# PocketSDR_Discovery.net
KiCad netlist of a schematic drawn in EAGLE
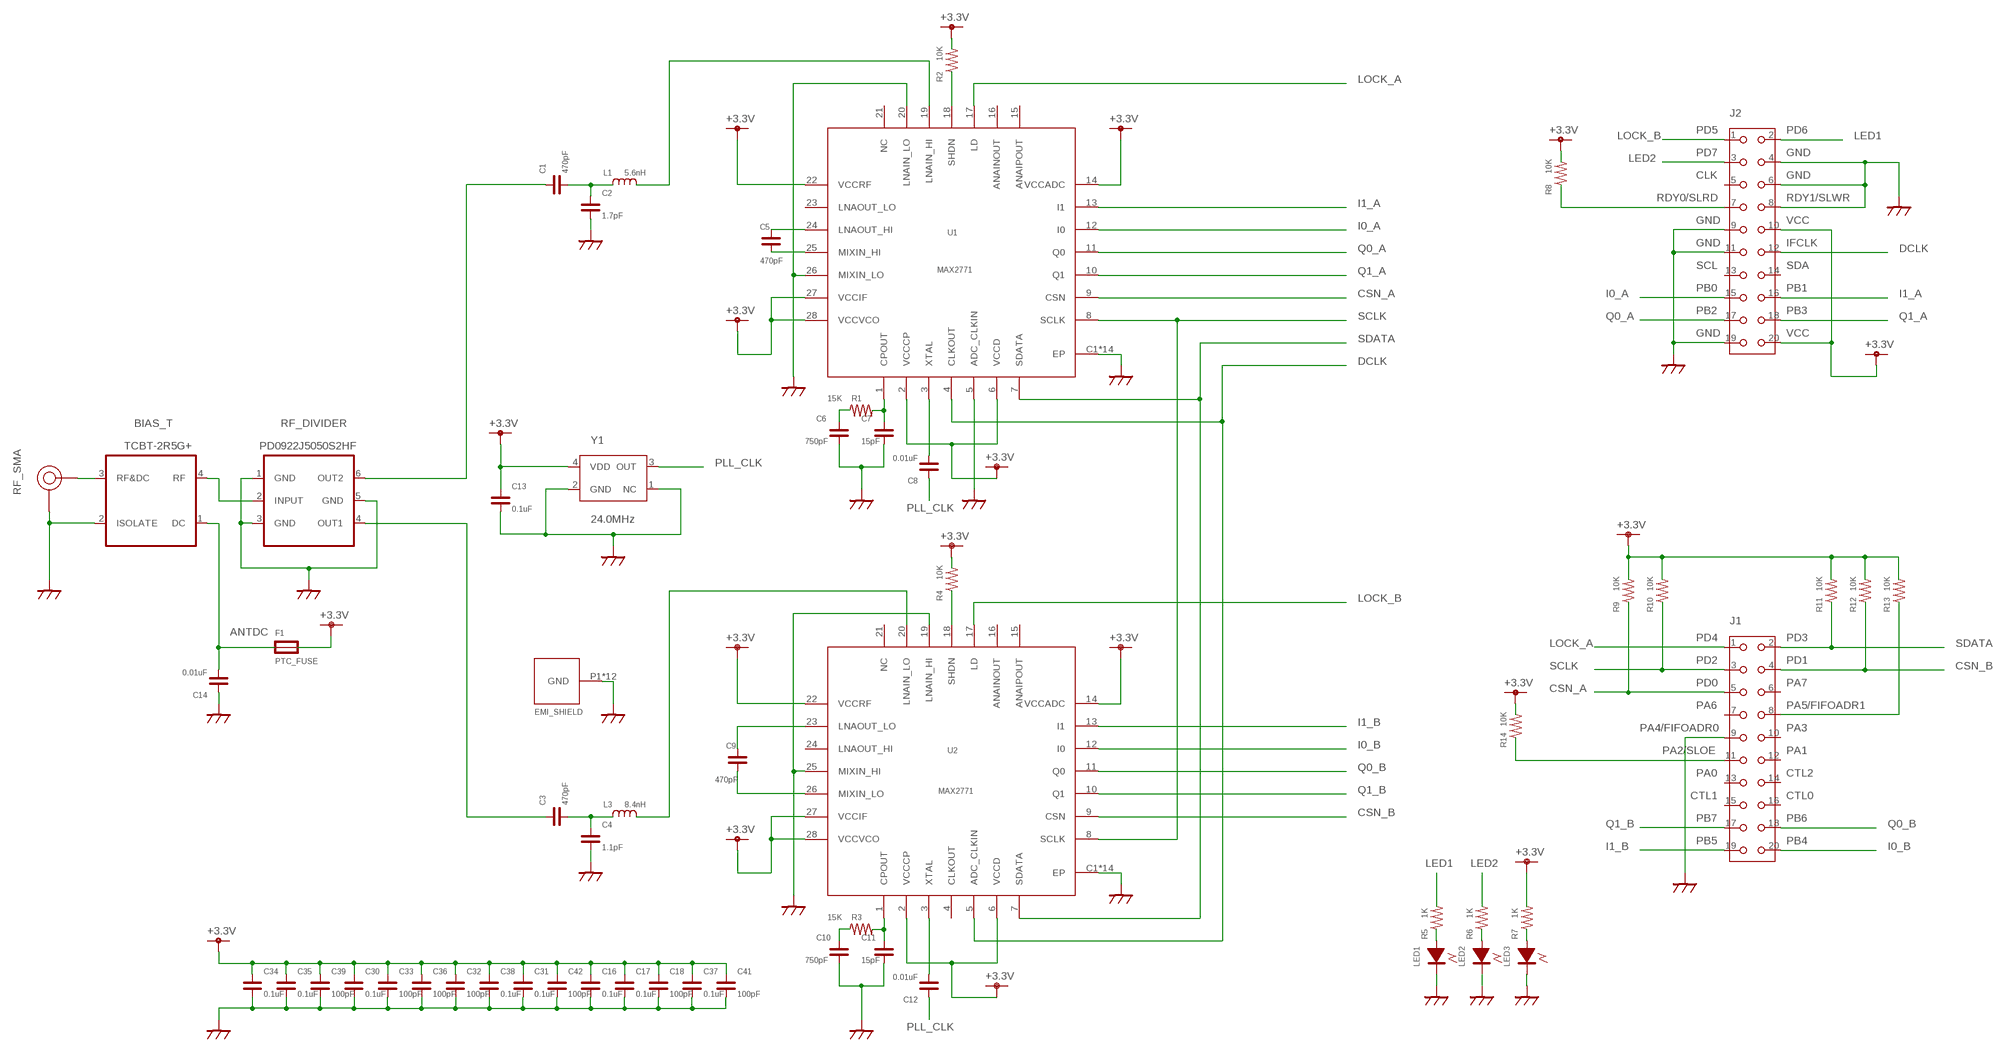
[diagram p0: schematic, sheet 1]

(export (version "E")
  (design (tool "Eeschema 10.0.6"))
  (components
    (comp (ref "BIAS_T")
      (value "TCBT-2R5G+")
      (footprint "eagle-import:BIAS_T")
      (libsource (lib "eagle-import") (part "BIAS_T"))
    )
    (comp (ref "C1")
      (value "470pF")
      (footprint "eagle-import:C1005")
      (libsource (lib "eagle-import") (part "C1005"))
    )
    (comp (ref "C2")
      (value "1.7pF")
      (footprint "eagle-import:C1005")
      (libsource (lib "eagle-import") (part "C1005"))
    )
    (comp (ref "C3")
      (value "470pF")
      (footprint "eagle-import:C1005")
      (libsource (lib "eagle-import") (part "C1005"))
    )
    (comp (ref "C4")
      (value "1.1pF")
      (footprint "eagle-import:C1005")
      (libsource (lib "eagle-import") (part "C1005"))
    )
    (comp (ref "C5")
      (value "470pF")
      (footprint "eagle-import:C1005")
      (libsource (lib "eagle-import") (part "C1005"))
    )
    (comp (ref "C6")
      (value "750pF")
      (footprint "eagle-import:C1005")
      (libsource (lib "eagle-import") (part "C1005"))
    )
    (comp (ref "C7")
      (value "15pF")
      (footprint "eagle-import:C1005")
      (libsource (lib "eagle-import") (part "C1005"))
    )
    (comp (ref "C8")
      (value "0.01uF")
      (footprint "eagle-import:C1005")
      (libsource (lib "eagle-import") (part "C1005"))
    )
    (comp (ref "C9")
      (value "470pF")
      (footprint "eagle-import:C1005")
      (libsource (lib "eagle-import") (part "C1005"))
    )
    (comp (ref "C10")
      (value "750pF")
      (footprint "eagle-import:C1005")
      (libsource (lib "eagle-import") (part "C1005"))
    )
    (comp (ref "C11")
      (value "15pF")
      (footprint "eagle-import:C1005")
      (libsource (lib "eagle-import") (part "C1005"))
    )
    (comp (ref "C12")
      (value "0.01uF")
      (footprint "eagle-import:C1005")
      (libsource (lib "eagle-import") (part "C1005"))
    )
    (comp (ref "C13")
      (value "0.1uF")
      (footprint "eagle-import:C1005")
      (libsource (lib "eagle-import") (part "C1005"))
    )
    (comp (ref "C14")
      (value "0.01uF")
      (footprint "eagle-import:C1005")
      (libsource (lib "eagle-import") (part "C1005"))
    )
    (comp (ref "C16")
      (value "0.1uF")
      (footprint "eagle-import:C1005")
      (libsource (lib "eagle-import") (part "C1005"))
    )
    (comp (ref "C17")
      (value "0.1uF")
      (footprint "eagle-import:C1005")
      (libsource (lib "eagle-import") (part "C1005"))
    )
    (comp (ref "C18")
      (value "100pF")
      (footprint "eagle-import:C1005")
      (libsource (lib "eagle-import") (part "C1005"))
    )
    (comp (ref "C30")
      (value "0.1uF")
      (footprint "eagle-import:C1005")
      (libsource (lib "eagle-import") (part "C1005"))
    )
    (comp (ref "C31")
      (value "0.1uF")
      (footprint "eagle-import:C1005")
      (libsource (lib "eagle-import") (part "C1005"))
    )
    (comp (ref "C32")
      (value "100pF")
      (footprint "eagle-import:C1005")
      (libsource (lib "eagle-import") (part "C1005"))
    )
    (comp (ref "C33")
      (value "100pF")
      (footprint "eagle-import:C1005")
      (libsource (lib "eagle-import") (part "C1005"))
    )
    (comp (ref "C34")
      (value "0.1uF")
      (footprint "eagle-import:C1005")
      (libsource (lib "eagle-import") (part "C1005"))
    )
    (comp (ref "C35")
      (value "0.1uF")
      (footprint "eagle-import:C1005")
      (libsource (lib "eagle-import") (part "C1005"))
    )
    (comp (ref "C36")
      (value "100pF")
      (footprint "eagle-import:C1005")
      (libsource (lib "eagle-import") (part "C1005"))
    )
    (comp (ref "C37")
      (value "0.1uF")
      (footprint "eagle-import:C1005")
      (libsource (lib "eagle-import") (part "C1005"))
    )
    (comp (ref "C38")
      (value "0.1uF")
      (footprint "eagle-import:C1005")
      (libsource (lib "eagle-import") (part "C1005"))
    )
    (comp (ref "C39")
      (value "100pF")
      (footprint "eagle-import:C1005")
      (libsource (lib "eagle-import") (part "C1005"))
    )
    (comp (ref "C41")
      (value "100pF")
      (footprint "eagle-import:C1005")
      (libsource (lib "eagle-import") (part "C1005"))
    )
    (comp (ref "C42")
      (value "100pF")
      (footprint "eagle-import:C1005")
      (libsource (lib "eagle-import") (part "C1005"))
    )
    (comp (ref "F1")
      (value "PTC_FUSE")
      (footprint "eagle-import:C1608")
      (libsource (lib "eagle-import") (part "PTC_FUSE"))
    )
    (comp (ref "J1")
      (value "PINH-2.54MM-20P")
      (footprint "eagle-import:PINH-2.54MM-20P")
      (libsource (lib "eagle-import") (part "PINH-2.54MM-20P"))
    )
    (comp (ref "J2")
      (value "PINH-2.54MM-20P")
      (footprint "eagle-import:PINH-2.54MM-20P")
      (libsource (lib "eagle-import") (part "PINH-2.54MM-20P"))
    )
    (comp (ref "L1")
      (value "5.6nH")
      (footprint "eagle-import:C1608")
      (libsource (lib "eagle-import") (part "L1608"))
    )
    (comp (ref "L3")
      (value "8.4nH")
      (footprint "eagle-import:C1608")
      (libsource (lib "eagle-import") (part "L1608"))
    )
    (comp (ref "LED1")
      (value "LED1608")
      (footprint "eagle-import:LED_1608")
      (libsource (lib "eagle-import") (part "LED1608"))
    )
    (comp (ref "LED2")
      (value "LED1608")
      (footprint "eagle-import:LED_1608")
      (libsource (lib "eagle-import") (part "LED1608"))
    )
    (comp (ref "LED3")
      (value "LED1608")
      (footprint "eagle-import:LED_1608")
      (libsource (lib "eagle-import") (part "LED1608"))
    )
    (comp (ref "R1")
      (value "15K")
      (footprint "eagle-import:C1005")
      (libsource (lib "eagle-import") (part "R1005"))
    )
    (comp (ref "R2")
      (value "10K")
      (footprint "eagle-import:C1005")
      (libsource (lib "eagle-import") (part "R1005"))
    )
    (comp (ref "R3")
      (value "15K")
      (footprint "eagle-import:C1005")
      (libsource (lib "eagle-import") (part "R1005"))
    )
    (comp (ref "R4")
      (value "10K")
      (footprint "eagle-import:C1005")
      (libsource (lib "eagle-import") (part "R1005"))
    )
    (comp (ref "R5")
      (value "1K")
      (footprint "eagle-import:C1005")
      (libsource (lib "eagle-import") (part "R1005"))
    )
    (comp (ref "R6")
      (value "1K")
      (footprint "eagle-import:C1005")
      (libsource (lib "eagle-import") (part "R1005"))
    )
    (comp (ref "R7")
      (value "1K")
      (footprint "eagle-import:C1005")
      (libsource (lib "eagle-import") (part "R1005"))
    )
    (comp (ref "R8")
      (value "10K")
      (footprint "eagle-import:C1005")
      (libsource (lib "eagle-import") (part "R1005"))
    )
    (comp (ref "R9")
      (value "10K")
      (footprint "eagle-import:C1005")
      (libsource (lib "eagle-import") (part "R1005"))
    )
    (comp (ref "R10")
      (value "10K")
      (footprint "eagle-import:C1005")
      (libsource (lib "eagle-import") (part "R1005"))
    )
    (comp (ref "R11")
      (value "10K")
      (footprint "eagle-import:C1005")
      (libsource (lib "eagle-import") (part "R1005"))
    )
    (comp (ref "R12")
      (value "10K")
      (footprint "eagle-import:C1005")
      (libsource (lib "eagle-import") (part "R1005"))
    )
    (comp (ref "R13")
      (value "10K")
      (footprint "eagle-import:C1005")
      (libsource (lib "eagle-import") (part "R1005"))
    )
    (comp (ref "R14")
      (value "10K")
      (footprint "eagle-import:C1005")
      (libsource (lib "eagle-import") (part "R1005"))
    )
    (comp (ref "RF-SHEILD-CASE")
      (value "BMI-S-202-F BMI-S-202-C")
      (footprint "eagle-import:BMI-S-202")
      (libsource (lib "eagle-import") (part "BMI-S-202"))
    )
    (comp (ref "RF_DIVIDER")
      (value "PD0922J5050S2HF")
      (footprint "eagle-import:RF_DIV")
      (libsource (lib "eagle-import") (part "RF_DIV"))
    )
    (comp (ref "RF_SMA")
      (value "SMA JACK EDGE MNT")
      (footprint "eagle-import:SMA-ANG")
      (libsource (lib "eagle-import") (part "SMA-ANG"))
    )
    (comp (ref "U1")
      (value "MAX2771")
      (footprint "eagle-import:TQFN28")
      (libsource (lib "eagle-import") (part "MAX2771"))
    )
    (comp (ref "U2")
      (value "MAX2771")
      (footprint "eagle-import:TQFN28")
      (libsource (lib "eagle-import") (part "MAX2771"))
    )
    (comp (ref "Y1")
      (value "24.0MHz")
      (footprint "eagle-import:TCXO2520")
      (libsource (lib "eagle-import") (part "TCXO2520"))
    )
  )
  (nets
    (net (code "1") (name "+3.3V") (class "Default")
      (node (ref "C13") (pin "1") (pinfunction "1_1") (pintype "passive"))
      (node (ref "C16") (pin "1") (pinfunction "1_1") (pintype "passive"))
      (node (ref "C17") (pin "1") (pinfunction "1_1") (pintype "passive"))
      (node (ref "C18") (pin "1") (pinfunction "1_1") (pintype "passive"))
      (node (ref "C30") (pin "1") (pinfunction "1_1") (pintype "passive"))
      (node (ref "C31") (pin "1") (pinfunction "1_1") (pintype "passive"))
      (node (ref "C32") (pin "1") (pinfunction "1_1") (pintype "passive"))
      (node (ref "C33") (pin "1") (pinfunction "1_1") (pintype "passive"))
      (node (ref "C34") (pin "1") (pinfunction "1_1") (pintype "passive"))
      (node (ref "C35") (pin "1") (pinfunction "1_1") (pintype "passive"))
      (node (ref "C36") (pin "1") (pinfunction "1_1") (pintype "passive"))
      (node (ref "C37") (pin "1") (pinfunction "1_1") (pintype "passive"))
      (node (ref "C38") (pin "1") (pinfunction "1_1") (pintype "passive"))
      (node (ref "C39") (pin "1") (pinfunction "1_1") (pintype "passive"))
      (node (ref "C41") (pin "1") (pinfunction "1_1") (pintype "passive"))
      (node (ref "C42") (pin "1") (pinfunction "1_1") (pintype "passive"))
      (node (ref "F1") (pin "2") (pinfunction "P$2_2") (pintype "bidirectional"))
      (node (ref "J2") (pin "10") (pinfunction "P10_10") (pintype "bidirectional"))
      (node (ref "J2") (pin "20") (pinfunction "P20_20") (pintype "bidirectional"))
      (node (ref "R10") (pin "2") (pinfunction "P$2_2") (pintype "passive"))
      (node (ref "R11") (pin "2") (pinfunction "P$2_2") (pintype "passive"))
      (node (ref "R12") (pin "2") (pinfunction "P$2_2") (pintype "passive"))
      (node (ref "R13") (pin "2") (pinfunction "P$2_2") (pintype "passive"))
      (node (ref "R14") (pin "2") (pinfunction "P$2_2") (pintype "passive"))
      (node (ref "R2") (pin "2") (pinfunction "P$2_2") (pintype "passive"))
      (node (ref "R4") (pin "2") (pinfunction "P$2_2") (pintype "passive"))
      (node (ref "R7") (pin "2") (pinfunction "P$2_2") (pintype "passive"))
      (node (ref "R8") (pin "2") (pinfunction "P$2_2") (pintype "passive"))
      (node (ref "R9") (pin "2") (pinfunction "P$2_2") (pintype "passive"))
      (node (ref "U1") (pin "14") (pinfunction "VCCADC_14") (pintype "power_in"))
      (node (ref "U1") (pin "2") (pinfunction "VCCCP_2") (pintype "power_in"))
      (node (ref "U1") (pin "22") (pinfunction "VCCRF_22") (pintype "power_in"))
      (node (ref "U1") (pin "27") (pinfunction "VCCIF_27") (pintype "power_in"))
      (node (ref "U1") (pin "28") (pinfunction "VCCVCO_28") (pintype "power_in"))
      (node (ref "U1") (pin "6") (pinfunction "VCCD_6") (pintype "power_in"))
      (node (ref "U2") (pin "14") (pinfunction "VCCADC_14") (pintype "power_in"))
      (node (ref "U2") (pin "2") (pinfunction "VCCCP_2") (pintype "power_in"))
      (node (ref "U2") (pin "22") (pinfunction "VCCRF_22") (pintype "power_in"))
      (node (ref "U2") (pin "27") (pinfunction "VCCIF_27") (pintype "power_in"))
      (node (ref "U2") (pin "28") (pinfunction "VCCVCO_28") (pintype "power_in"))
      (node (ref "U2") (pin "6") (pinfunction "VCCD_6") (pintype "power_in"))
      (node (ref "Y1") (pin "4") (pinfunction "VDD_4") (pintype "bidirectional"))
    )
    (net (code "2") (name "/ANTDC") (class "Default")
      (node (ref "BIAS_T") (pin "1") (pinfunction "DC_1") (pintype "bidirectional"))
      (node (ref "C14") (pin "2") (pinfunction "2_2") (pintype "passive"))
      (node (ref "F1") (pin "1") (pinfunction "P$1_1") (pintype "bidirectional"))
    )
    (net (code "3") (name "/CSN_A") (class "Default")
      (node (ref "J1") (pin "5") (pinfunction "P5_5") (pintype "bidirectional"))
      (node (ref "R9") (pin "1") (pinfunction "P$1_1") (pintype "passive"))
      (node (ref "U1") (pin "9") (pinfunction "CSN_9") (pintype "input"))
    )
    (net (code "4") (name "/CSN_B") (class "Default")
      (node (ref "J1") (pin "4") (pinfunction "P4_4") (pintype "bidirectional"))
      (node (ref "R12") (pin "1") (pinfunction "P$1_1") (pintype "passive"))
      (node (ref "U2") (pin "9") (pinfunction "CSN_9") (pintype "input"))
    )
    (net (code "5") (name "/DCLK") (class "Default")
      (node (ref "J2") (pin "12") (pinfunction "P12_12") (pintype "bidirectional"))
      (node (ref "U1") (pin "4") (pinfunction "CLKOUT_4") (pintype "bidirectional"))
      (node (ref "U2") (pin "5") (pinfunction "ADC_CLKIN_5") (pintype "bidirectional"))
    )
    (net (code "6") (name "/I0_A") (class "Default")
      (node (ref "J2") (pin "15") (pinfunction "P15_15") (pintype "bidirectional"))
      (node (ref "U1") (pin "12") (pinfunction "I0_12") (pintype "output"))
    )
    (net (code "7") (name "/I0_B") (class "Default")
      (node (ref "J1") (pin "20") (pinfunction "P20_20") (pintype "bidirectional"))
      (node (ref "U2") (pin "12") (pinfunction "I0_12") (pintype "output"))
    )
    (net (code "8") (name "/I1_A") (class "Default")
      (node (ref "J2") (pin "16") (pinfunction "P16_16") (pintype "bidirectional"))
      (node (ref "U1") (pin "13") (pinfunction "I1_13") (pintype "output"))
    )
    (net (code "9") (name "/I1_B") (class "Default")
      (node (ref "J1") (pin "19") (pinfunction "P19_19") (pintype "bidirectional"))
      (node (ref "U2") (pin "13") (pinfunction "I1_13") (pintype "output"))
    )
    (net (code "10") (name "/LED1") (class "Default")
      (node (ref "J2") (pin "2") (pinfunction "P2_2") (pintype "bidirectional"))
      (node (ref "R5") (pin "2") (pinfunction "P$2_2") (pintype "passive"))
    )
    (net (code "11") (name "/LED2") (class "Default")
      (node (ref "J2") (pin "3") (pinfunction "P3_3") (pintype "bidirectional"))
      (node (ref "R6") (pin "2") (pinfunction "P$2_2") (pintype "passive"))
    )
    (net (code "12") (name "/LOCK_A") (class "Default")
      (node (ref "J1") (pin "1") (pinfunction "P1_1") (pintype "bidirectional"))
      (node (ref "U1") (pin "17") (pinfunction "LD_17") (pintype "output"))
    )
    (net (code "13") (name "/LOCK_B") (class "Default")
      (node (ref "J2") (pin "1") (pinfunction "P1_1") (pintype "bidirectional"))
      (node (ref "U2") (pin "17") (pinfunction "LD_17") (pintype "output"))
    )
    (net (code "14") (name "/PLL_CLK") (class "Default")
      (node (ref "C12") (pin "1") (pinfunction "1_1") (pintype "passive"))
      (node (ref "C8") (pin "1") (pinfunction "1_1") (pintype "passive"))
      (node (ref "Y1") (pin "3") (pinfunction "OUT_3") (pintype "bidirectional"))
    )
    (net (code "15") (name "/Q0_A") (class "Default")
      (node (ref "J2") (pin "17") (pinfunction "P17_17") (pintype "bidirectional"))
      (node (ref "U1") (pin "11") (pinfunction "Q0_11") (pintype "output"))
    )
    (net (code "16") (name "/Q0_B") (class "Default")
      (node (ref "J1") (pin "18") (pinfunction "P18_18") (pintype "bidirectional"))
      (node (ref "U2") (pin "11") (pinfunction "Q0_11") (pintype "output"))
    )
    (net (code "17") (name "/Q1_A") (class "Default")
      (node (ref "J2") (pin "18") (pinfunction "P18_18") (pintype "bidirectional"))
      (node (ref "U1") (pin "10") (pinfunction "Q1_10") (pintype "output"))
    )
    (net (code "18") (name "/Q1_B") (class "Default")
      (node (ref "J1") (pin "17") (pinfunction "P17_17") (pintype "bidirectional"))
      (node (ref "U2") (pin "10") (pinfunction "Q1_10") (pintype "output"))
    )
    (net (code "19") (name "/SCLK") (class "Default")
      (node (ref "J1") (pin "3") (pinfunction "P3_3") (pintype "bidirectional"))
      (node (ref "R10") (pin "1") (pinfunction "P$1_1") (pintype "passive"))
      (node (ref "U1") (pin "8") (pinfunction "SCLK_8") (pintype "input"))
      (node (ref "U2") (pin "8") (pinfunction "SCLK_8") (pintype "input"))
    )
    (net (code "20") (name "/SDATA") (class "Default")
      (node (ref "J1") (pin "2") (pinfunction "P2_2") (pintype "bidirectional"))
      (node (ref "R11") (pin "1") (pinfunction "P$1_1") (pintype "passive"))
      (node (ref "U1") (pin "7") (pinfunction "SDATA_7") (pintype "bidirectional"))
      (node (ref "U2") (pin "7") (pinfunction "SDATA_7") (pintype "bidirectional"))
    )
    (net (code "21") (name "GND") (class "Default")
      (node (ref "BIAS_T") (pin "2") (pinfunction "ISOLATE_2") (pintype "bidirectional"))
      (node (ref "C10") (pin "2") (pinfunction "2_2") (pintype "passive"))
      (node (ref "C11") (pin "2") (pinfunction "2_2") (pintype "passive"))
      (node (ref "C13") (pin "2") (pinfunction "2_2") (pintype "passive"))
      (node (ref "C14") (pin "1") (pinfunction "1_1") (pintype "passive"))
      (node (ref "C16") (pin "2") (pinfunction "2_2") (pintype "passive"))
      (node (ref "C17") (pin "2") (pinfunction "2_2") (pintype "passive"))
      (node (ref "C18") (pin "2") (pinfunction "2_2") (pintype "passive"))
      (node (ref "C2") (pin "1") (pinfunction "1_1") (pintype "passive"))
      (node (ref "C30") (pin "2") (pinfunction "2_2") (pintype "passive"))
      (node (ref "C31") (pin "2") (pinfunction "2_2") (pintype "passive"))
      (node (ref "C32") (pin "2") (pinfunction "2_2") (pintype "passive"))
      (node (ref "C33") (pin "2") (pinfunction "2_2") (pintype "passive"))
      (node (ref "C34") (pin "2") (pinfunction "2_2") (pintype "passive"))
      (node (ref "C35") (pin "2") (pinfunction "2_2") (pintype "passive"))
      (node (ref "C36") (pin "2") (pinfunction "2_2") (pintype "passive"))
      (node (ref "C37") (pin "2") (pinfunction "2_2") (pintype "passive"))
      (node (ref "C38") (pin "2") (pinfunction "2_2") (pintype "passive"))
      (node (ref "C39") (pin "2") (pinfunction "2_2") (pintype "passive"))
      (node (ref "C4") (pin "2") (pinfunction "2_2") (pintype "passive"))
      (node (ref "C41") (pin "2") (pinfunction "2_2") (pintype "passive"))
      (node (ref "C42") (pin "2") (pinfunction "2_2") (pintype "passive"))
      (node (ref "C6") (pin "2") (pinfunction "2_2") (pintype "passive"))
      (node (ref "C7") (pin "2") (pinfunction "2_2") (pintype "passive"))
      (node (ref "J1") (pin "9") (pinfunction "P9_9") (pintype "bidirectional"))
      (node (ref "J2") (pin "11") (pinfunction "P11_11") (pintype "bidirectional"))
      (node (ref "J2") (pin "19") (pinfunction "P19_19") (pintype "bidirectional"))
      (node (ref "J2") (pin "4") (pinfunction "P4_4") (pintype "bidirectional"))
      (node (ref "J2") (pin "6") (pinfunction "P6_6") (pintype "bidirectional"))
      (node (ref "J2") (pin "8") (pinfunction "P8_8") (pintype "bidirectional"))
      (node (ref "J2") (pin "9") (pinfunction "P9_9") (pintype "bidirectional"))
      (node (ref "LED1") (pin "2") (pinfunction "P$2_2") (pintype "passive"))
      (node (ref "LED2") (pin "2") (pinfunction "P$2_2") (pintype "passive"))
      (node (ref "LED3") (pin "2") (pinfunction "P$2_2") (pintype "passive"))
      (node (ref "RF-SHEILD-CASE") (pin "P1") (pinfunction "GND_P1") (pintype "bidirectional"))
      (node (ref "RF-SHEILD-CASE") (pin "P10") (pinfunction "GND_P10") (pintype "bidirectional"))
      (node (ref "RF-SHEILD-CASE") (pin "P11") (pinfunction "GND_P11") (pintype "bidirectional"))
      (node (ref "RF-SHEILD-CASE") (pin "P12") (pinfunction "GND_P12") (pintype "bidirectional"))
      (node (ref "RF-SHEILD-CASE") (pin "P2") (pinfunction "GND_P2") (pintype "bidirectional"))
      (node (ref "RF-SHEILD-CASE") (pin "P3") (pinfunction "GND_P3") (pintype "bidirectional"))
      (node (ref "RF-SHEILD-CASE") (pin "P4") (pinfunction "GND_P4") (pintype "bidirectional"))
      (node (ref "RF-SHEILD-CASE") (pin "P5") (pinfunction "GND_P5") (pintype "bidirectional"))
      (node (ref "RF-SHEILD-CASE") (pin "P6") (pinfunction "GND_P6") (pintype "bidirectional"))
      (node (ref "RF-SHEILD-CASE") (pin "P7") (pinfunction "GND_P7") (pintype "bidirectional"))
      (node (ref "RF-SHEILD-CASE") (pin "P8") (pinfunction "GND_P8") (pintype "bidirectional"))
      (node (ref "RF-SHEILD-CASE") (pin "P9") (pinfunction "GND_P9") (pintype "bidirectional"))
      (node (ref "RF_DIVIDER") (pin "1") (pinfunction "GND_1") (pintype "bidirectional"))
      (node (ref "RF_DIVIDER") (pin "3") (pinfunction "GND_3") (pintype "bidirectional"))
      (node (ref "RF_DIVIDER") (pin "5") (pinfunction "GND_5") (pintype "bidirectional"))
      (node (ref "RF_SMA") (pin "P2") (pinfunction "GND_P2") (pintype "passive"))
      (node (ref "RF_SMA") (pin "P3") (pinfunction "GND_P3") (pintype "passive"))
      (node (ref "RF_SMA") (pin "P4") (pinfunction "GND_P4") (pintype "passive"))
      (node (ref "RF_SMA") (pin "P5") (pinfunction "GND_P5") (pintype "passive"))
      (node (ref "U1") (pin "20") (pinfunction "LNAIN_LO_20") (pintype "bidirectional"))
      (node (ref "U1") (pin "26") (pinfunction "MIXIN_LO_26") (pintype "input"))
      (node (ref "U1") (pin "5") (pinfunction "ADC_CLKIN_5") (pintype "bidirectional"))
      (node (ref "U1") (pin "C1") (pinfunction "EP_C1") (pintype "power_in"))
      (node (ref "U1") (pin "C2") (pinfunction "EP_C2") (pintype "power_in"))
      (node (ref "U1") (pin "C3") (pinfunction "EP_C3") (pintype "power_in"))
      (node (ref "U1") (pin "C4") (pinfunction "EP_C4") (pintype "power_in"))
      (node (ref "U1") (pin "EP") (pinfunction "EP_EP") (pintype "power_in"))
      (node (ref "U1") (pin "V1") (pinfunction "EP_V1") (pintype "power_in"))
      (node (ref "U1") (pin "V2") (pinfunction "EP_V2") (pintype "power_in"))
      (node (ref "U1") (pin "V3") (pinfunction "EP_V3") (pintype "power_in"))
      (node (ref "U1") (pin "V4") (pinfunction "EP_V4") (pintype "power_in"))
      (node (ref "U1") (pin "V5") (pinfunction "EP_V5") (pintype "power_in"))
      (node (ref "U1") (pin "V6") (pinfunction "EP_V6") (pintype "power_in"))
      (node (ref "U1") (pin "V7") (pinfunction "EP_V7") (pintype "power_in"))
      (node (ref "U1") (pin "V8") (pinfunction "EP_V8") (pintype "power_in"))
      (node (ref "U1") (pin "V9") (pinfunction "EP_V9") (pintype "power_in"))
      (node (ref "U2") (pin "19") (pinfunction "LNAIN_HI_19") (pintype "bidirectional"))
      (node (ref "U2") (pin "25") (pinfunction "MIXIN_HI_25") (pintype "input"))
      (node (ref "U2") (pin "C1") (pinfunction "EP_C1") (pintype "power_in"))
      (node (ref "U2") (pin "C2") (pinfunction "EP_C2") (pintype "power_in"))
      (node (ref "U2") (pin "C3") (pinfunction "EP_C3") (pintype "power_in"))
      (node (ref "U2") (pin "C4") (pinfunction "EP_C4") (pintype "power_in"))
      (node (ref "U2") (pin "EP") (pinfunction "EP_EP") (pintype "power_in"))
      (node (ref "U2") (pin "V1") (pinfunction "EP_V1") (pintype "power_in"))
      (node (ref "U2") (pin "V2") (pinfunction "EP_V2") (pintype "power_in"))
      (node (ref "U2") (pin "V3") (pinfunction "EP_V3") (pintype "power_in"))
      (node (ref "U2") (pin "V4") (pinfunction "EP_V4") (pintype "power_in"))
      (node (ref "U2") (pin "V5") (pinfunction "EP_V5") (pintype "power_in"))
      (node (ref "U2") (pin "V6") (pinfunction "EP_V6") (pintype "power_in"))
      (node (ref "U2") (pin "V7") (pinfunction "EP_V7") (pintype "power_in"))
      (node (ref "U2") (pin "V8") (pinfunction "EP_V8") (pintype "power_in"))
      (node (ref "U2") (pin "V9") (pinfunction "EP_V9") (pintype "power_in"))
      (node (ref "Y1") (pin "1") (pinfunction "NC_1") (pintype "bidirectional"))
      (node (ref "Y1") (pin "2") (pinfunction "GND_2") (pintype "bidirectional"))
    )
    (net (code "22") (name "Net-(BIAS_T-RF&DC)") (class "Default")
      (node (ref "BIAS_T") (pin "3") (pinfunction "RF&DC_3") (pintype "bidirectional"))
      (node (ref "RF_SMA") (pin "P1") (pinfunction "RF_P1") (pintype "passive"))
    )
    (net (code "23") (name "Net-(BIAS_T-RF)") (class "Default")
      (node (ref "BIAS_T") (pin "4") (pinfunction "RF_4") (pintype "bidirectional"))
      (node (ref "RF_DIVIDER") (pin "2") (pinfunction "INPUT_2") (pintype "input"))
    )
    (net (code "24") (name "Net-(J1-P8)") (class "Default")
      (node (ref "J1") (pin "8") (pinfunction "P8_8") (pintype "bidirectional"))
      (node (ref "R13") (pin "1") (pinfunction "P$1_1") (pintype "passive"))
    )
    (net (code "25") (name "Net-(J1-P11)") (class "Default")
      (node (ref "J1") (pin "11") (pinfunction "P11_11") (pintype "bidirectional"))
      (node (ref "R14") (pin "1") (pinfunction "P$1_1") (pintype "passive"))
    )
    (net (code "26") (name "Net-(J2-P7)") (class "Default")
      (node (ref "J2") (pin "7") (pinfunction "P7_7") (pintype "bidirectional"))
      (node (ref "R8") (pin "1") (pinfunction "P$1_1") (pintype "passive"))
    )
    (net (code "27") (name "Net-(L1-P$1)") (class "Default")
      (node (ref "C1") (pin "2") (pinfunction "2_2") (pintype "passive"))
      (node (ref "C2") (pin "2") (pinfunction "2_2") (pintype "passive"))
      (node (ref "L1") (pin "1") (pinfunction "P$1_1") (pintype "passive"))
    )
    (net (code "28") (name "Net-(L1-P$2)") (class "Default")
      (node (ref "L1") (pin "2") (pinfunction "P$2_2") (pintype "passive"))
      (node (ref "U1") (pin "19") (pinfunction "LNAIN_HI_19") (pintype "bidirectional"))
    )
    (net (code "29") (name "Net-(L3-P$1)") (class "Default")
      (node (ref "C3") (pin "2") (pinfunction "2_2") (pintype "passive"))
      (node (ref "C4") (pin "1") (pinfunction "1_1") (pintype "passive"))
      (node (ref "L3") (pin "1") (pinfunction "P$1_1") (pintype "passive"))
    )
    (net (code "30") (name "Net-(L3-P$2)") (class "Default")
      (node (ref "L3") (pin "2") (pinfunction "P$2_2") (pintype "passive"))
      (node (ref "U2") (pin "20") (pinfunction "LNAIN_LO_20") (pintype "bidirectional"))
    )
    (net (code "31") (name "Net-(LED1-+)") (class "Default")
      (node (ref "LED1") (pin "1") (pinfunction "+_1") (pintype "passive"))
      (node (ref "R5") (pin "1") (pinfunction "P$1_1") (pintype "passive"))
    )
    (net (code "32") (name "Net-(LED2-+)") (class "Default")
      (node (ref "LED2") (pin "1") (pinfunction "+_1") (pintype "passive"))
      (node (ref "R6") (pin "1") (pinfunction "P$1_1") (pintype "passive"))
    )
    (net (code "33") (name "Net-(LED3-+)") (class "Default")
      (node (ref "LED3") (pin "1") (pinfunction "+_1") (pintype "passive"))
      (node (ref "R7") (pin "1") (pinfunction "P$1_1") (pintype "passive"))
    )
    (net (code "34") (name "Net-(R1-P$1)") (class "Default")
      (node (ref "C6") (pin "1") (pinfunction "1_1") (pintype "passive"))
      (node (ref "R1") (pin "1") (pinfunction "P$1_1") (pintype "passive"))
    )
    (net (code "35") (name "Net-(R1-P$2)") (class "Default")
      (node (ref "C7") (pin "1") (pinfunction "1_1") (pintype "passive"))
      (node (ref "R1") (pin "2") (pinfunction "P$2_2") (pintype "passive"))
      (node (ref "U1") (pin "1") (pinfunction "CPOUT_1") (pintype "bidirectional"))
    )
    (net (code "36") (name "Net-(R2-P$1)") (class "Default")
      (node (ref "R2") (pin "1") (pinfunction "P$1_1") (pintype "passive"))
      (node (ref "U1") (pin "18") (pinfunction "SHDN_18") (pintype "bidirectional"))
    )
    (net (code "37") (name "Net-(R3-P$1)") (class "Default")
      (node (ref "C10") (pin "1") (pinfunction "1_1") (pintype "passive"))
      (node (ref "R3") (pin "1") (pinfunction "P$1_1") (pintype "passive"))
    )
    (net (code "38") (name "Net-(R3-P$2)") (class "Default")
      (node (ref "C11") (pin "1") (pinfunction "1_1") (pintype "passive"))
      (node (ref "R3") (pin "2") (pinfunction "P$2_2") (pintype "passive"))
      (node (ref "U2") (pin "1") (pinfunction "CPOUT_1") (pintype "bidirectional"))
    )
    (net (code "39") (name "Net-(R4-P$1)") (class "Default")
      (node (ref "R4") (pin "1") (pinfunction "P$1_1") (pintype "passive"))
      (node (ref "U2") (pin "18") (pinfunction "SHDN_18") (pintype "bidirectional"))
    )
    (net (code "40") (name "Net-(RF_DIVIDER-OUT1)") (class "Default")
      (node (ref "C3") (pin "1") (pinfunction "1_1") (pintype "passive"))
      (node (ref "RF_DIVIDER") (pin "4") (pinfunction "OUT1_4") (pintype "bidirectional"))
    )
    (net (code "41") (name "Net-(RF_DIVIDER-OUT2)") (class "Default")
      (node (ref "C1") (pin "1") (pinfunction "1_1") (pintype "passive"))
      (node (ref "RF_DIVIDER") (pin "6") (pinfunction "OUT2_6") (pintype "bidirectional"))
    )
    (net (code "42") (name "Net-(U1-LNAOUT_HI)") (class "Default")
      (node (ref "C5") (pin "1") (pinfunction "1_1") (pintype "passive"))
      (node (ref "U1") (pin "24") (pinfunction "LNAOUT_HI_24") (pintype "output"))
    )
    (net (code "43") (name "Net-(U1-MIXIN_HI)") (class "Default")
      (node (ref "C5") (pin "2") (pinfunction "2_2") (pintype "passive"))
      (node (ref "U1") (pin "25") (pinfunction "MIXIN_HI_25") (pintype "input"))
    )
    (net (code "44") (name "Net-(U1-XTAL)") (class "Default")
      (node (ref "C8") (pin "2") (pinfunction "2_2") (pintype "passive"))
      (node (ref "U1") (pin "3") (pinfunction "XTAL_3") (pintype "bidirectional"))
    )
    (net (code "45") (name "Net-(U2-LNAOUT_LO)") (class "Default")
      (node (ref "C9") (pin "1") (pinfunction "1_1") (pintype "passive"))
      (node (ref "U2") (pin "23") (pinfunction "LNAOUT_LO_23") (pintype "output"))
    )
    (net (code "46") (name "Net-(U2-MIXIN_LO)") (class "Default")
      (node (ref "C9") (pin "2") (pinfunction "2_2") (pintype "passive"))
      (node (ref "U2") (pin "26") (pinfunction "MIXIN_LO_26") (pintype "input"))
    )
    (net (code "47") (name "Net-(U2-XTAL)") (class "Default")
      (node (ref "C12") (pin "2") (pinfunction "2_2") (pintype "passive"))
      (node (ref "U2") (pin "3") (pinfunction "XTAL_3") (pintype "bidirectional"))
    )
    (net (code "48") (name "unconnected-(J1-P6-Pad6)") (class "Default")
      (node (ref "J1") (pin "6") (pinfunction "P6_6") (pintype "bidirectional"))
    )
    (net (code "49") (name "unconnected-(J1-P7-Pad7)") (class "Default")
      (node (ref "J1") (pin "7") (pinfunction "P7_7") (pintype "bidirectional"))
    )
    (net (code "50") (name "unconnected-(J1-P10-Pad10)") (class "Default")
      (node (ref "J1") (pin "10") (pinfunction "P10_10") (pintype "bidirectional"))
    )
    (net (code "51") (name "unconnected-(J1-P12-Pad12)") (class "Default")
      (node (ref "J1") (pin "12") (pinfunction "P12_12") (pintype "bidirectional"))
    )
    (net (code "52") (name "unconnected-(J1-P13-Pad13)") (class "Default")
      (node (ref "J1") (pin "13") (pinfunction "P13_13") (pintype "bidirectional"))
    )
    (net (code "53") (name "unconnected-(J1-P14-Pad14)") (class "Default")
      (node (ref "J1") (pin "14") (pinfunction "P14_14") (pintype "bidirectional"))
    )
    (net (code "54") (name "unconnected-(J1-P15-Pad15)") (class "Default")
      (node (ref "J1") (pin "15") (pinfunction "P15_15") (pintype "bidirectional"))
    )
    (net (code "55") (name "unconnected-(J1-P16-Pad16)") (class "Default")
      (node (ref "J1") (pin "16") (pinfunction "P16_16") (pintype "bidirectional"))
    )
    (net (code "56") (name "unconnected-(J2-P5-Pad5)") (class "Default")
      (node (ref "J2") (pin "5") (pinfunction "P5_5") (pintype "bidirectional"))
    )
    (net (code "57") (name "unconnected-(J2-P13-Pad13)") (class "Default")
      (node (ref "J2") (pin "13") (pinfunction "P13_13") (pintype "bidirectional"))
    )
    (net (code "58") (name "unconnected-(J2-P14-Pad14)") (class "Default")
      (node (ref "J2") (pin "14") (pinfunction "P14_14") (pintype "bidirectional"))
    )
    (net (code "59") (name "unconnected-(U1-ANAINOUT-Pad16)") (class "Default")
      (node (ref "U1") (pin "16") (pinfunction "ANAINOUT_16") (pintype "bidirectional"))
    )
    (net (code "60") (name "unconnected-(U1-ANAIPOUT-Pad15)") (class "Default")
      (node (ref "U1") (pin "15") (pinfunction "ANAIPOUT_15") (pintype "bidirectional"))
    )
    (net (code "61") (name "unconnected-(U1-LNAOUT_LO-Pad23)") (class "Default")
      (node (ref "U1") (pin "23") (pinfunction "LNAOUT_LO_23") (pintype "output"))
    )
    (net (code "62") (name "unconnected-(U1-NC-Pad21)") (class "Default")
      (node (ref "U1") (pin "21") (pinfunction "NC_21") (pintype "no_connect"))
    )
    (net (code "63") (name "unconnected-(U2-ANAINOUT-Pad16)") (class "Default")
      (node (ref "U2") (pin "16") (pinfunction "ANAINOUT_16") (pintype "bidirectional"))
    )
    (net (code "64") (name "unconnected-(U2-ANAIPOUT-Pad15)") (class "Default")
      (node (ref "U2") (pin "15") (pinfunction "ANAIPOUT_15") (pintype "bidirectional"))
    )
    (net (code "65") (name "unconnected-(U2-CLKOUT-Pad4)") (class "Default")
      (node (ref "U2") (pin "4") (pinfunction "CLKOUT_4") (pintype "bidirectional"))
    )
    (net (code "66") (name "unconnected-(U2-LNAOUT_HI-Pad24)") (class "Default")
      (node (ref "U2") (pin "24") (pinfunction "LNAOUT_HI_24") (pintype "output"))
    )
    (net (code "67") (name "unconnected-(U2-NC-Pad21)") (class "Default")
      (node (ref "U2") (pin "21") (pinfunction "NC_21") (pintype "no_connect"))
    )
  )
)
